# Conductor_S000A.net
KiCad netlist of a schematic drawn in EAGLE
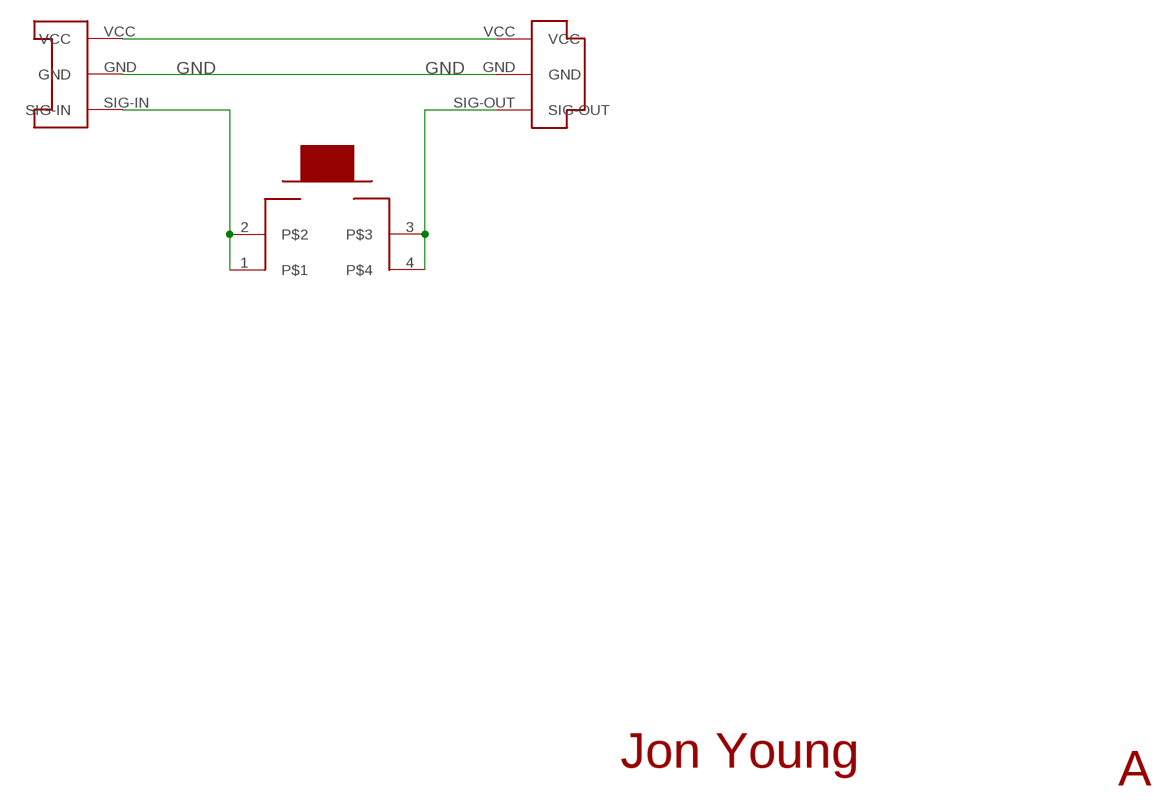
[diagram p0: schematic, sheet 1]

(export (version "E")
  (design (tool "Eeschema 10.0.6"))
  (components
    (comp (ref "U$1")
      (value "CONN-PLUG-3POS-3MM")
      (footprint "eagle-import:PLUG-3POS-3MM-SMD")
      (libsource (lib "eagle-import") (part "CONN-PLUG-3POS-3MM"))
    )
    (comp (ref "U$2")
      (value "CONN-SOCKET-3POS-3MM")
      (footprint "eagle-import:SOCKET-3POS-3MM-SMD")
      (libsource (lib "eagle-import") (part "CONN-SOCKET-3POS-3MM"))
    )
    (comp (ref "U$3")
      (value "PUSH_BUTTON")
      (footprint "eagle-import:ESWITCH-TL3300CF260Q")
      (libsource (lib "eagle-import") (part "PUSH_BUTTON"))
    )
  )
  (nets
    (net (code "1") (name "/GND") (class "Default")
      (node (ref "U$1") (pin "GND") (pinfunction "GND_GND") (pintype "power_in"))
      (node (ref "U$2") (pin "GND") (pinfunction "GND_GND") (pintype "power_in"))
    )
    (net (code "2") (name "Net-(U$1-PadVCC)") (class "Default")
      (node (ref "U$1") (pin "VCC") (pinfunction "VCC_VCC") (pintype "power_in"))
      (node (ref "U$2") (pin "VCC") (pinfunction "VCC_VCC") (pintype "power_in"))
    )
    (net (code "3") (name "Net-(U$3-P$1)") (class "Default")
      (node (ref "U$2") (pin "SIG-IN") (pinfunction "SIG-IN_SIG-IN") (pintype "bidirectional"))
      (node (ref "U$3") (pin "1") (pinfunction "P$1_1") (pintype "bidirectional"))
      (node (ref "U$3") (pin "2") (pinfunction "P$2_2") (pintype "bidirectional"))
    )
    (net (code "4") (name "Net-(U$3-P$3)") (class "Default")
      (node (ref "U$1") (pin "SIG-OUT") (pinfunction "SIG-OUT_SIG-OUT") (pintype "bidirectional"))
      (node (ref "U$3") (pin "3") (pinfunction "P$3_3") (pintype "bidirectional"))
      (node (ref "U$3") (pin "4") (pinfunction "P$4_4") (pintype "bidirectional"))
    )
  )
)
